# RGB-TestPatternGenerator.net
KiCad netlist of a schematic drawn in EAGLE
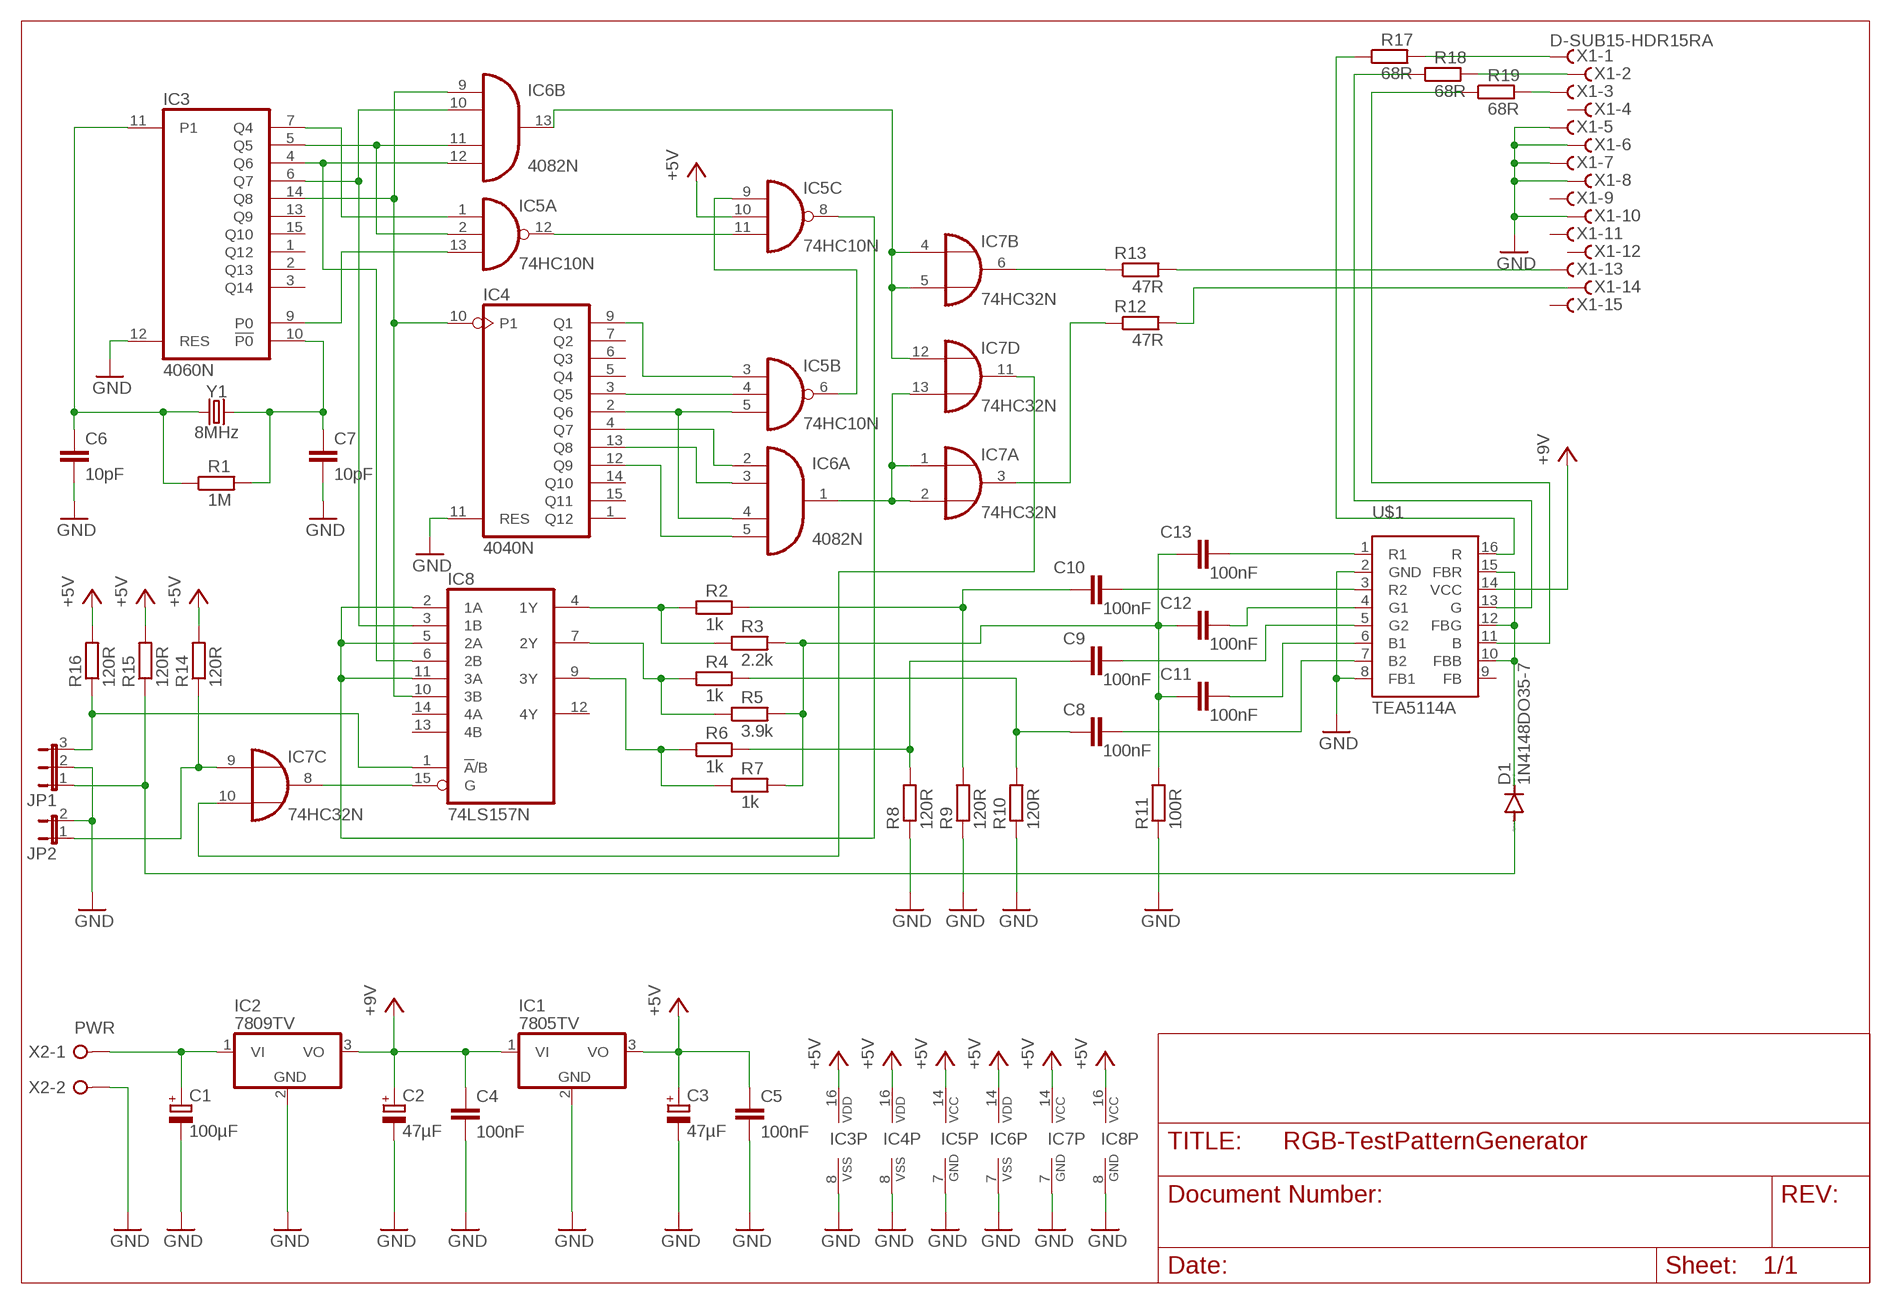
[diagram p0: schematic, sheet 1]

(export (version "E")
  (design (tool "Eeschema 10.0.6"))
  (components
    (comp (ref "C1")
      (value "100µF")
      (footprint "eagle-import:E2,5-6E")
      (libsource (lib "eagle-import") (part "CPOL-EUE2,5-6E"))
    )
    (comp (ref "C2")
      (value "47µF")
      (footprint "eagle-import:E2-5")
      (libsource (lib "eagle-import") (part "CPOL-EUE2-5"))
    )
    (comp (ref "C3")
      (value "47µF")
      (footprint "eagle-import:E2-5")
      (libsource (lib "eagle-import") (part "CPOL-EUE2-5"))
    )
    (comp (ref "C4")
      (value "100nF")
      (footprint "eagle-import:C050-024X044")
      (libsource (lib "eagle-import") (part "C-EU050-024X044"))
    )
    (comp (ref "C5")
      (value "100nF")
      (footprint "eagle-import:C050-024X044")
      (libsource (lib "eagle-import") (part "C-EU050-024X044"))
    )
    (comp (ref "C6")
      (value "10pF")
      (footprint "eagle-import:C050-024X044")
      (libsource (lib "eagle-import") (part "C-EU050-024X044"))
    )
    (comp (ref "C7")
      (value "10pF")
      (footprint "eagle-import:C050-024X044")
      (libsource (lib "eagle-import") (part "C-EU050-024X044"))
    )
    (comp (ref "C8")
      (value "100nF")
      (footprint "eagle-import:C050-024X044")
      (libsource (lib "eagle-import") (part "C-EU050-024X044"))
    )
    (comp (ref "C9")
      (value "100nF")
      (footprint "eagle-import:C050-024X044")
      (libsource (lib "eagle-import") (part "C-EU050-024X044"))
    )
    (comp (ref "C10")
      (value "100nF")
      (footprint "eagle-import:C050-024X044")
      (libsource (lib "eagle-import") (part "C-EU050-024X044"))
    )
    (comp (ref "C11")
      (value "100nF")
      (footprint "eagle-import:C050-024X044")
      (libsource (lib "eagle-import") (part "C-EU050-024X044"))
    )
    (comp (ref "C12")
      (value "100nF")
      (footprint "eagle-import:C050-024X044")
      (libsource (lib "eagle-import") (part "C-EU050-024X044"))
    )
    (comp (ref "C13")
      (value "100nF")
      (footprint "eagle-import:C050-024X044")
      (libsource (lib "eagle-import") (part "C-EU050-024X044"))
    )
    (comp (ref "D1")
      (value "1N4148DO35-7")
      (footprint "eagle-import:DO35-7")
      (libsource (lib "eagle-import") (part "1N4148DO35-7"))
    )
    (comp (ref "IC1")
      (value "7805TV")
      (footprint "eagle-import:TO220V")
      (libsource (lib "eagle-import") (part "78TV05"))
    )
    (comp (ref "IC2")
      (value "7809TV")
      (footprint "eagle-import:TO220V")
      (libsource (lib "eagle-import") (part "78TV05"))
    )
    (comp (ref "IC3")
      (value "4060N")
      (footprint "eagle-import:DIL16")
      (libsource (lib "eagle-import") (part "4060N"))
    )
    (comp (ref "IC4")
      (value "4040N")
      (footprint "eagle-import:DIL16")
      (libsource (lib "eagle-import") (part "4040N"))
    )
    (comp (ref "IC5")
      (value "74HC10N")
      (footprint "eagle-import:DIL14")
      (libsource (lib "eagle-import") (part "7410NHC"))
    )
    (comp (ref "IC6")
      (value "4082N")
      (footprint "eagle-import:DIL14")
      (libsource (lib "eagle-import") (part "4082N"))
    )
    (comp (ref "IC7")
      (value "74HC32N")
      (footprint "eagle-import:DIL14")
      (libsource (lib "eagle-import") (part "7432NHC"))
    )
    (comp (ref "IC8")
      (value "74LS157N")
      (footprint "eagle-import:DIL16")
      (libsource (lib "eagle-import") (part "74157NLS"))
    )
    (comp (ref "JP1")
      (value "JP2E")
      (footprint "eagle-import:JP2")
      (libsource (lib "eagle-import") (part "JP2E"))
    )
    (comp (ref "JP2")
      (value "JP1E")
      (footprint "eagle-import:JP1")
      (libsource (lib "eagle-import") (part "JP1E"))
    )
    (comp (ref "R1")
      (value "1M")
      (footprint "eagle-import:0207_10")
      (libsource (lib "eagle-import") (part "R-EU_0207/10"))
    )
    (comp (ref "R2")
      (value "1k")
      (footprint "eagle-import:0207_10")
      (libsource (lib "eagle-import") (part "R-EU_0207/10"))
    )
    (comp (ref "R3")
      (value "2.2k")
      (footprint "eagle-import:0207_10")
      (libsource (lib "eagle-import") (part "R-EU_0207/10"))
    )
    (comp (ref "R4")
      (value "1k")
      (footprint "eagle-import:0207_10")
      (libsource (lib "eagle-import") (part "R-EU_0207/10"))
    )
    (comp (ref "R5")
      (value "3.9k")
      (footprint "eagle-import:0207_10")
      (libsource (lib "eagle-import") (part "R-EU_0207/10"))
    )
    (comp (ref "R6")
      (value "1k")
      (footprint "eagle-import:0207_10")
      (libsource (lib "eagle-import") (part "R-EU_0207/10"))
    )
    (comp (ref "R7")
      (value "1k")
      (footprint "eagle-import:0207_10")
      (libsource (lib "eagle-import") (part "R-EU_0207/10"))
    )
    (comp (ref "R8")
      (value "120R")
      (footprint "eagle-import:0207_10")
      (libsource (lib "eagle-import") (part "R-EU_0207/10"))
    )
    (comp (ref "R9")
      (value "120R")
      (footprint "eagle-import:0207_10")
      (libsource (lib "eagle-import") (part "R-EU_0207/10"))
    )
    (comp (ref "R10")
      (value "120R")
      (footprint "eagle-import:0207_10")
      (libsource (lib "eagle-import") (part "R-EU_0207/10"))
    )
    (comp (ref "R11")
      (value "100R")
      (footprint "eagle-import:0207_10")
      (libsource (lib "eagle-import") (part "R-EU_0207/10"))
    )
    (comp (ref "R12")
      (value "47R")
      (footprint "eagle-import:0207_10")
      (libsource (lib "eagle-import") (part "R-EU_0207/10"))
    )
    (comp (ref "R13")
      (value "47R")
      (footprint "eagle-import:0207_10")
      (libsource (lib "eagle-import") (part "R-EU_0207/10"))
    )
    (comp (ref "R14")
      (value "120R")
      (footprint "eagle-import:0207_10")
      (libsource (lib "eagle-import") (part "R-EU_0207/10"))
    )
    (comp (ref "R15")
      (value "120R")
      (footprint "eagle-import:0207_10")
      (libsource (lib "eagle-import") (part "R-EU_0207/10"))
    )
    (comp (ref "R16")
      (value "120R")
      (footprint "eagle-import:0207_10")
      (libsource (lib "eagle-import") (part "R-EU_0207/10"))
    )
    (comp (ref "R17")
      (value "68R")
      (footprint "eagle-import:0207_10")
      (libsource (lib "eagle-import") (part "R-EU_0207/10"))
    )
    (comp (ref "R18")
      (value "68R")
      (footprint "eagle-import:0207_10")
      (libsource (lib "eagle-import") (part "R-EU_0207/10"))
    )
    (comp (ref "R19")
      (value "68R")
      (footprint "eagle-import:0207_10")
      (libsource (lib "eagle-import") (part "R-EU_0207/10"))
    )
    (comp (ref "U$1")
      (value "TEA5114A")
      (footprint "eagle-import:TEA5114A")
      (libsource (lib "eagle-import") (part "RGBTEA5114A"))
    )
    (comp (ref "X1")
      (value "D-SUB15-HDR15RA")
      (footprint "eagle-import:HDR15RA")
      (libsource (lib "eagle-import") (part "D-SUB15-HDR15RA"))
    )
    (comp (ref "X2")
      (value "PWR")
      (footprint "eagle-import:W237-132")
      (libsource (lib "eagle-import") (part "W237-02P"))
    )
    (comp (ref "Y1")
      (value "8MHz")
      (footprint "eagle-import:HC49US")
      (libsource (lib "eagle-import") (part "CRYSTALPTH-HC49US"))
    )
  )
  (nets
    (net (code "1") (name "+5V") (class "Default")
      (node (ref "C3") (pin "+") (pinfunction "+_+") (pintype "passive"))
      (node (ref "C5") (pin "1") (pinfunction "1_1") (pintype "passive"))
      (node (ref "IC1") (pin "3") (pinfunction "VO_3") (pintype "passive"))
      (node (ref "IC3") (pin "16") (pinfunction "VDD_16") (pintype "power_in"))
      (node (ref "IC4") (pin "16") (pinfunction "VDD_16") (pintype "power_in"))
      (node (ref "IC5") (pin "10") (pinfunction "I1_10") (pintype "input"))
      (node (ref "IC5") (pin "14") (pinfunction "VCC_14") (pintype "power_in"))
      (node (ref "IC6") (pin "14") (pinfunction "VDD_14") (pintype "power_in"))
      (node (ref "IC7") (pin "14") (pinfunction "VCC_14") (pintype "power_in"))
      (node (ref "IC8") (pin "16") (pinfunction "VCC_16") (pintype "power_in"))
      (node (ref "R14") (pin "2") (pinfunction "2_2") (pintype "passive"))
      (node (ref "R15") (pin "2") (pinfunction "2_2") (pintype "passive"))
      (node (ref "R16") (pin "2") (pinfunction "2_2") (pintype "passive"))
    )
    (net (code "2") (name "+9V") (class "Default")
      (node (ref "C2") (pin "+") (pinfunction "+_+") (pintype "passive"))
      (node (ref "C4") (pin "1") (pinfunction "1_1") (pintype "passive"))
      (node (ref "IC1") (pin "1") (pinfunction "VI_1") (pintype "input"))
      (node (ref "IC2") (pin "3") (pinfunction "VO_3") (pintype "passive"))
      (node (ref "U$1") (pin "14") (pinfunction "VCC_14") (pintype "power_in"))
    )
    (net (code "3") (name "GND") (class "Default")
      (node (ref "C1") (pin "-") (pinfunction "-_-") (pintype "passive"))
      (node (ref "C2") (pin "-") (pinfunction "-_-") (pintype "passive"))
      (node (ref "C3") (pin "-") (pinfunction "-_-") (pintype "passive"))
      (node (ref "C4") (pin "2") (pinfunction "2_2") (pintype "passive"))
      (node (ref "C5") (pin "2") (pinfunction "2_2") (pintype "passive"))
      (node (ref "C6") (pin "2") (pinfunction "2_2") (pintype "passive"))
      (node (ref "C7") (pin "2") (pinfunction "2_2") (pintype "passive"))
      (node (ref "IC1") (pin "2") (pinfunction "GND_2") (pintype "passive"))
      (node (ref "IC2") (pin "2") (pinfunction "GND_2") (pintype "passive"))
      (node (ref "IC3") (pin "12") (pinfunction "RES_12") (pintype "input"))
      (node (ref "IC3") (pin "8") (pinfunction "VSS_8") (pintype "power_in"))
      (node (ref "IC4") (pin "11") (pinfunction "RES_11") (pintype "input"))
      (node (ref "IC4") (pin "8") (pinfunction "VSS_8") (pintype "power_in"))
      (node (ref "IC5") (pin "7") (pinfunction "GND_7") (pintype "power_in"))
      (node (ref "IC6") (pin "7") (pinfunction "VSS_7") (pintype "power_in"))
      (node (ref "IC7") (pin "7") (pinfunction "GND_7") (pintype "power_in"))
      (node (ref "IC8") (pin "8") (pinfunction "GND_8") (pintype "power_in"))
      (node (ref "JP1") (pin "2") (pinfunction "2_2") (pintype "passive"))
      (node (ref "JP2") (pin "2") (pinfunction "2_2") (pintype "passive"))
      (node (ref "R10") (pin "1") (pinfunction "1_1") (pintype "passive"))
      (node (ref "R11") (pin "1") (pinfunction "1_1") (pintype "passive"))
      (node (ref "R8") (pin "1") (pinfunction "1_1") (pintype "passive"))
      (node (ref "R9") (pin "1") (pinfunction "1_1") (pintype "passive"))
      (node (ref "U$1") (pin "2") (pinfunction "GND_2") (pintype "bidirectional"))
      (node (ref "U$1") (pin "8") (pinfunction "FB1_8") (pintype "input"))
      (node (ref "X1") (pin "10") (pinfunction "F_10") (pintype "passive"))
      (node (ref "X1") (pin "5") (pinfunction "F_5") (pintype "passive"))
      (node (ref "X1") (pin "6") (pinfunction "F_6") (pintype "passive"))
      (node (ref "X1") (pin "7") (pinfunction "F_7") (pintype "passive"))
      (node (ref "X1") (pin "8") (pinfunction "F_8") (pintype "passive"))
      (node (ref "X2") (pin "2") (pinfunction "KL_2") (pintype "passive"))
    )
    (net (code "4") (name "Net-(C8-Pad1)") (class "Default")
      (node (ref "C8") (pin "1") (pinfunction "1_1") (pintype "passive"))
      (node (ref "R10") (pin "2") (pinfunction "2_2") (pintype "passive"))
      (node (ref "R4") (pin "2") (pinfunction "2_2") (pintype "passive"))
    )
    (net (code "5") (name "Net-(C9-Pad1)") (class "Default")
      (node (ref "C9") (pin "1") (pinfunction "1_1") (pintype "passive"))
      (node (ref "R6") (pin "2") (pinfunction "2_2") (pintype "passive"))
      (node (ref "R8") (pin "2") (pinfunction "2_2") (pintype "passive"))
    )
    (net (code "6") (name "Net-(C10-Pad1)") (class "Default")
      (node (ref "C10") (pin "1") (pinfunction "1_1") (pintype "passive"))
      (node (ref "R2") (pin "2") (pinfunction "2_2") (pintype "passive"))
      (node (ref "R9") (pin "2") (pinfunction "2_2") (pintype "passive"))
    )
    (net (code "7") (name "Net-(C11-Pad1)") (class "Default")
      (node (ref "C11") (pin "1") (pinfunction "1_1") (pintype "passive"))
      (node (ref "C12") (pin "1") (pinfunction "1_1") (pintype "passive"))
      (node (ref "C13") (pin "1") (pinfunction "1_1") (pintype "passive"))
      (node (ref "R11") (pin "2") (pinfunction "2_2") (pintype "passive"))
      (node (ref "R3") (pin "2") (pinfunction "2_2") (pintype "passive"))
      (node (ref "R5") (pin "2") (pinfunction "2_2") (pintype "passive"))
      (node (ref "R7") (pin "2") (pinfunction "2_2") (pintype "passive"))
    )
    (net (code "8") (name "Net-(D1-PadA)") (class "Default")
      (node (ref "D1") (pin "A") (pinfunction "A_A") (pintype "passive"))
      (node (ref "JP1") (pin "1") (pinfunction "1_1") (pintype "passive"))
      (node (ref "R15") (pin "1") (pinfunction "1_1") (pintype "passive"))
    )
    (net (code "9") (name "Net-(IC2-VI)") (class "Default")
      (node (ref "C1") (pin "+") (pinfunction "+_+") (pintype "passive"))
      (node (ref "IC2") (pin "1") (pinfunction "VI_1") (pintype "input"))
      (node (ref "X2") (pin "1") (pinfunction "KL_1") (pintype "passive"))
    )
    (net (code "10") (name "Net-(IC3A-P0)") (class "Default")
      (node (ref "IC3") (pin "9") (pinfunction "P0_9") (pintype "output"))
      (node (ref "IC5") (pin "13") (pinfunction "I2_13") (pintype "input"))
    )
    (net (code "11") (name "Net-(IC3A-P1)") (class "Default")
      (node (ref "C6") (pin "1") (pinfunction "1_1") (pintype "passive"))
      (node (ref "IC3") (pin "11") (pinfunction "P1_11") (pintype "input"))
      (node (ref "R1") (pin "1") (pinfunction "1_1") (pintype "passive"))
      (node (ref "Y1") (pin "1") (pinfunction "1_1") (pintype "passive"))
    )
    (net (code "12") (name "Net-(IC3A-Q4)") (class "Default")
      (node (ref "IC3") (pin "7") (pinfunction "Q4_7") (pintype "output"))
      (node (ref "IC5") (pin "1") (pinfunction "I0_1") (pintype "input"))
    )
    (net (code "13") (name "Net-(IC3A-Q5)") (class "Default")
      (node (ref "IC3") (pin "5") (pinfunction "Q5_5") (pintype "output"))
      (node (ref "IC5") (pin "2") (pinfunction "I1_2") (pintype "input"))
      (node (ref "IC6") (pin "11") (pinfunction "I2_11") (pintype "input"))
    )
    (net (code "14") (name "Net-(IC3A-Q6)") (class "Default")
      (node (ref "IC3") (pin "4") (pinfunction "Q6_4") (pintype "output"))
      (node (ref "IC6") (pin "12") (pinfunction "I3_12") (pintype "input"))
      (node (ref "IC8") (pin "6") (pinfunction "2B_6") (pintype "input"))
    )
    (net (code "15") (name "Net-(IC3A-Q7)") (class "Default")
      (node (ref "IC3") (pin "6") (pinfunction "Q7_6") (pintype "output"))
      (node (ref "IC6") (pin "10") (pinfunction "I1_10") (pintype "input"))
      (node (ref "IC8") (pin "3") (pinfunction "1B_3") (pintype "input"))
    )
    (net (code "16") (name "Net-(IC3A-Q8)") (class "Default")
      (node (ref "IC3") (pin "14") (pinfunction "Q8_14") (pintype "output"))
      (node (ref "IC4") (pin "10") (pinfunction "P1_10") (pintype "input"))
      (node (ref "IC6") (pin "9") (pinfunction "I0_9") (pintype "input"))
      (node (ref "IC8") (pin "10") (pinfunction "3B_10") (pintype "input"))
    )
    (net (code "17") (name "Net-(IC3A-~{P0})") (class "Default")
      (node (ref "C7") (pin "1") (pinfunction "1_1") (pintype "passive"))
      (node (ref "IC3") (pin "10") (pinfunction "~{P0}_10") (pintype "output"))
      (node (ref "R1") (pin "2") (pinfunction "2_2") (pintype "passive"))
      (node (ref "Y1") (pin "2") (pinfunction "2_2") (pintype "passive"))
    )
    (net (code "18") (name "Net-(IC4A-Q1)") (class "Default")
      (node (ref "IC4") (pin "9") (pinfunction "Q1_9") (pintype "output"))
      (node (ref "IC5") (pin "3") (pinfunction "I0_3") (pintype "input"))
    )
    (net (code "19") (name "Net-(IC4A-Q5)") (class "Default")
      (node (ref "IC4") (pin "3") (pinfunction "Q5_3") (pintype "output"))
      (node (ref "IC5") (pin "4") (pinfunction "I1_4") (pintype "input"))
    )
    (net (code "20") (name "Net-(IC4A-Q6)") (class "Default")
      (node (ref "IC4") (pin "2") (pinfunction "Q6_2") (pintype "output"))
      (node (ref "IC5") (pin "5") (pinfunction "I2_5") (pintype "input"))
      (node (ref "IC6") (pin "4") (pinfunction "I2_4") (pintype "input"))
    )
    (net (code "21") (name "Net-(IC4A-Q7)") (class "Default")
      (node (ref "IC4") (pin "4") (pinfunction "Q7_4") (pintype "output"))
      (node (ref "IC6") (pin "2") (pinfunction "I0_2") (pintype "input"))
    )
    (net (code "22") (name "Net-(IC4A-Q8)") (class "Default")
      (node (ref "IC4") (pin "13") (pinfunction "Q8_13") (pintype "output"))
      (node (ref "IC6") (pin "3") (pinfunction "I1_3") (pintype "input"))
    )
    (net (code "23") (name "Net-(IC4A-Q9)") (class "Default")
      (node (ref "IC4") (pin "12") (pinfunction "Q9_12") (pintype "output"))
      (node (ref "IC6") (pin "5") (pinfunction "I3_5") (pintype "input"))
    )
    (net (code "24") (name "Net-(IC5A-O)") (class "Default")
      (node (ref "IC5") (pin "11") (pinfunction "I2_11") (pintype "input"))
      (node (ref "IC5") (pin "12") (pinfunction "O_12") (pintype "output"))
    )
    (net (code "25") (name "Net-(IC5B-O)") (class "Default")
      (node (ref "IC5") (pin "6") (pinfunction "O_6") (pintype "output"))
      (node (ref "IC5") (pin "9") (pinfunction "I0_9") (pintype "input"))
    )
    (net (code "26") (name "Net-(IC5C-O)") (class "Default")
      (node (ref "IC5") (pin "8") (pinfunction "O_8") (pintype "output"))
      (node (ref "IC8") (pin "11") (pinfunction "3A_11") (pintype "input"))
      (node (ref "IC8") (pin "2") (pinfunction "1A_2") (pintype "input"))
      (node (ref "IC8") (pin "5") (pinfunction "2A_5") (pintype "input"))
    )
    (net (code "27") (name "Net-(IC6A-O)") (class "Default")
      (node (ref "IC6") (pin "1") (pinfunction "O_1") (pintype "output"))
      (node (ref "IC7") (pin "1") (pinfunction "I0_1") (pintype "input"))
      (node (ref "IC7") (pin "13") (pinfunction "I1_13") (pintype "input"))
      (node (ref "IC7") (pin "2") (pinfunction "I1_2") (pintype "input"))
    )
    (net (code "28") (name "Net-(IC6B-O)") (class "Default")
      (node (ref "IC6") (pin "13") (pinfunction "O_13") (pintype "output"))
      (node (ref "IC7") (pin "12") (pinfunction "I0_12") (pintype "input"))
      (node (ref "IC7") (pin "4") (pinfunction "I0_4") (pintype "input"))
      (node (ref "IC7") (pin "5") (pinfunction "I1_5") (pintype "input"))
    )
    (net (code "29") (name "Net-(IC7A-O)") (class "Default")
      (node (ref "IC7") (pin "3") (pinfunction "O_3") (pintype "output"))
      (node (ref "R12") (pin "1") (pinfunction "1_1") (pintype "passive"))
    )
    (net (code "30") (name "Net-(IC7B-O)") (class "Default")
      (node (ref "IC7") (pin "6") (pinfunction "O_6") (pintype "output"))
      (node (ref "R13") (pin "1") (pinfunction "1_1") (pintype "passive"))
    )
    (net (code "31") (name "Net-(IC7C-I0)") (class "Default")
      (node (ref "IC7") (pin "9") (pinfunction "I0_9") (pintype "input"))
      (node (ref "JP2") (pin "1") (pinfunction "1_1") (pintype "passive"))
      (node (ref "R14") (pin "1") (pinfunction "1_1") (pintype "passive"))
    )
    (net (code "32") (name "Net-(IC7C-I1)") (class "Default")
      (node (ref "IC7") (pin "10") (pinfunction "I1_10") (pintype "input"))
      (node (ref "IC7") (pin "11") (pinfunction "O_11") (pintype "output"))
    )
    (net (code "33") (name "Net-(IC7C-O)") (class "Default")
      (node (ref "IC7") (pin "8") (pinfunction "O_8") (pintype "output"))
      (node (ref "IC8") (pin "15") (pinfunction "G_15") (pintype "input"))
    )
    (net (code "34") (name "Net-(IC8A-1Y)") (class "Default")
      (node (ref "IC8") (pin "4") (pinfunction "1Y_4") (pintype "output"))
      (node (ref "R2") (pin "1") (pinfunction "1_1") (pintype "passive"))
      (node (ref "R3") (pin "1") (pinfunction "1_1") (pintype "passive"))
    )
    (net (code "35") (name "Net-(IC8A-2Y)") (class "Default")
      (node (ref "IC8") (pin "7") (pinfunction "2Y_7") (pintype "output"))
      (node (ref "R4") (pin "1") (pinfunction "1_1") (pintype "passive"))
      (node (ref "R5") (pin "1") (pinfunction "1_1") (pintype "passive"))
    )
    (net (code "36") (name "Net-(IC8A-3Y)") (class "Default")
      (node (ref "IC8") (pin "9") (pinfunction "3Y_9") (pintype "output"))
      (node (ref "R6") (pin "1") (pinfunction "1_1") (pintype "passive"))
      (node (ref "R7") (pin "1") (pinfunction "1_1") (pintype "passive"))
    )
    (net (code "37") (name "Net-(IC8A-~{A}{slash}B)") (class "Default")
      (node (ref "IC8") (pin "1") (pinfunction "~{A}/B_1") (pintype "input"))
      (node (ref "JP1") (pin "3") (pinfunction "3_3") (pintype "passive"))
      (node (ref "R16") (pin "1") (pinfunction "1_1") (pintype "passive"))
    )
    (net (code "38") (name "Net-(U$1-B)") (class "Default")
      (node (ref "R19") (pin "1") (pinfunction "1_1") (pintype "passive"))
      (node (ref "U$1") (pin "11") (pinfunction "B_11") (pintype "output"))
    )
    (net (code "39") (name "Net-(U$1-B1)") (class "Default")
      (node (ref "C11") (pin "2") (pinfunction "2_2") (pintype "passive"))
      (node (ref "U$1") (pin "6") (pinfunction "B1_6") (pintype "input"))
    )
    (net (code "40") (name "Net-(U$1-B2)") (class "Default")
      (node (ref "C8") (pin "2") (pinfunction "2_2") (pintype "passive"))
      (node (ref "U$1") (pin "7") (pinfunction "B2_7") (pintype "input"))
    )
    (net (code "41") (name "Net-(U$1-FBB)") (class "Default")
      (node (ref "D1") (pin "C") (pinfunction "C_C") (pintype "passive"))
      (node (ref "U$1") (pin "10") (pinfunction "FBB_10") (pintype "input"))
      (node (ref "U$1") (pin "12") (pinfunction "FBG_12") (pintype "input"))
      (node (ref "U$1") (pin "15") (pinfunction "FBR_15") (pintype "input"))
    )
    (net (code "42") (name "Net-(U$1-G)") (class "Default")
      (node (ref "R18") (pin "1") (pinfunction "1_1") (pintype "passive"))
      (node (ref "U$1") (pin "13") (pinfunction "G_13") (pintype "output"))
    )
    (net (code "43") (name "Net-(U$1-G1)") (class "Default")
      (node (ref "C12") (pin "2") (pinfunction "2_2") (pintype "passive"))
      (node (ref "U$1") (pin "4") (pinfunction "G1_4") (pintype "input"))
    )
    (net (code "44") (name "Net-(U$1-G2)") (class "Default")
      (node (ref "C9") (pin "2") (pinfunction "2_2") (pintype "passive"))
      (node (ref "U$1") (pin "5") (pinfunction "G2_5") (pintype "input"))
    )
    (net (code "45") (name "Net-(U$1-R)") (class "Default")
      (node (ref "R17") (pin "1") (pinfunction "1_1") (pintype "passive"))
      (node (ref "U$1") (pin "16") (pinfunction "R_16") (pintype "output"))
    )
    (net (code "46") (name "Net-(U$1-R1)") (class "Default")
      (node (ref "C13") (pin "2") (pinfunction "2_2") (pintype "passive"))
      (node (ref "U$1") (pin "1") (pinfunction "R1_1") (pintype "input"))
    )
    (net (code "47") (name "Net-(U$1-R2)") (class "Default")
      (node (ref "C10") (pin "2") (pinfunction "2_2") (pintype "passive"))
      (node (ref "U$1") (pin "3") (pinfunction "R2_3") (pintype "input"))
    )
    (net (code "48") (name "Net-(X1A-F)") (class "Default")
      (node (ref "R17") (pin "2") (pinfunction "2_2") (pintype "passive"))
      (node (ref "X1") (pin "1") (pinfunction "F_1") (pintype "passive"))
    )
    (net (code "49") (name "Net-(X1E-F)") (class "Default")
      (node (ref "R13") (pin "2") (pinfunction "2_2") (pintype "passive"))
      (node (ref "X1") (pin "13") (pinfunction "F_13") (pintype "passive"))
    )
    (net (code "50") (name "Net-(X1F-F)") (class "Default")
      (node (ref "R12") (pin "2") (pinfunction "2_2") (pintype "passive"))
      (node (ref "X1") (pin "14") (pinfunction "F_14") (pintype "passive"))
    )
    (net (code "51") (name "Net-(X1H-F)") (class "Default")
      (node (ref "R18") (pin "2") (pinfunction "2_2") (pintype "passive"))
      (node (ref "X1") (pin "2") (pinfunction "F_2") (pintype "passive"))
    )
    (net (code "52") (name "Net-(X1I-F)") (class "Default")
      (node (ref "R19") (pin "2") (pinfunction "2_2") (pintype "passive"))
      (node (ref "X1") (pin "3") (pinfunction "F_3") (pintype "passive"))
    )
    (net (code "53") (name "unconnected-(IC3A-Q9-Pad13)") (class "Default")
      (node (ref "IC3") (pin "13") (pinfunction "Q9_13") (pintype "output"))
    )
    (net (code "54") (name "unconnected-(IC3A-Q10-Pad15)") (class "Default")
      (node (ref "IC3") (pin "15") (pinfunction "Q10_15") (pintype "output"))
    )
    (net (code "55") (name "unconnected-(IC3A-Q12-Pad1)") (class "Default")
      (node (ref "IC3") (pin "1") (pinfunction "Q12_1") (pintype "output"))
    )
    (net (code "56") (name "unconnected-(IC3A-Q13-Pad2)") (class "Default")
      (node (ref "IC3") (pin "2") (pinfunction "Q13_2") (pintype "output"))
    )
    (net (code "57") (name "unconnected-(IC3A-Q14-Pad3)") (class "Default")
      (node (ref "IC3") (pin "3") (pinfunction "Q14_3") (pintype "output"))
    )
    (net (code "58") (name "unconnected-(IC4A-Q2-Pad7)") (class "Default")
      (node (ref "IC4") (pin "7") (pinfunction "Q2_7") (pintype "output"))
    )
    (net (code "59") (name "unconnected-(IC4A-Q3-Pad6)") (class "Default")
      (node (ref "IC4") (pin "6") (pinfunction "Q3_6") (pintype "output"))
    )
    (net (code "60") (name "unconnected-(IC4A-Q4-Pad5)") (class "Default")
      (node (ref "IC4") (pin "5") (pinfunction "Q4_5") (pintype "output"))
    )
    (net (code "61") (name "unconnected-(IC4A-Q10-Pad14)") (class "Default")
      (node (ref "IC4") (pin "14") (pinfunction "Q10_14") (pintype "output"))
    )
    (net (code "62") (name "unconnected-(IC4A-Q11-Pad15)") (class "Default")
      (node (ref "IC4") (pin "15") (pinfunction "Q11_15") (pintype "output"))
    )
    (net (code "63") (name "unconnected-(IC4A-Q12-Pad1)") (class "Default")
      (node (ref "IC4") (pin "1") (pinfunction "Q12_1") (pintype "output"))
    )
    (net (code "64") (name "unconnected-(IC8A-4A-Pad14)") (class "Default")
      (node (ref "IC8") (pin "14") (pinfunction "4A_14") (pintype "input"))
    )
    (net (code "65") (name "unconnected-(IC8A-4B-Pad13)") (class "Default")
      (node (ref "IC8") (pin "13") (pinfunction "4B_13") (pintype "input"))
    )
    (net (code "66") (name "unconnected-(IC8A-4Y-Pad12)") (class "Default")
      (node (ref "IC8") (pin "12") (pinfunction "4Y_12") (pintype "output"))
    )
    (net (code "67") (name "unconnected-(U$1-FB-Pad9)") (class "Default")
      (node (ref "U$1") (pin "9") (pinfunction "FB_9") (pintype "output"))
    )
    (net (code "68") (name "unconnected-(X1C-F-Pad11)") (class "Default")
      (node (ref "X1") (pin "11") (pinfunction "F_11") (pintype "passive"))
    )
    (net (code "69") (name "unconnected-(X1D-F-Pad12)") (class "Default")
      (node (ref "X1") (pin "12") (pinfunction "F_12") (pintype "passive"))
    )
    (net (code "70") (name "unconnected-(X1G-F-Pad15)") (class "Default")
      (node (ref "X1") (pin "15") (pinfunction "F_15") (pintype "passive"))
    )
    (net (code "71") (name "unconnected-(X1J-F-Pad4)") (class "Default")
      (node (ref "X1") (pin "4") (pinfunction "F_4") (pintype "passive"))
    )
    (net (code "72") (name "unconnected-(X1O-F-Pad9)") (class "Default")
      (node (ref "X1") (pin "9") (pinfunction "F_9") (pintype "passive"))
    )
  )
)
